# 05-GPS_IMU_SENSORS.net
KiCad netlist of a schematic drawn in Altium Designer
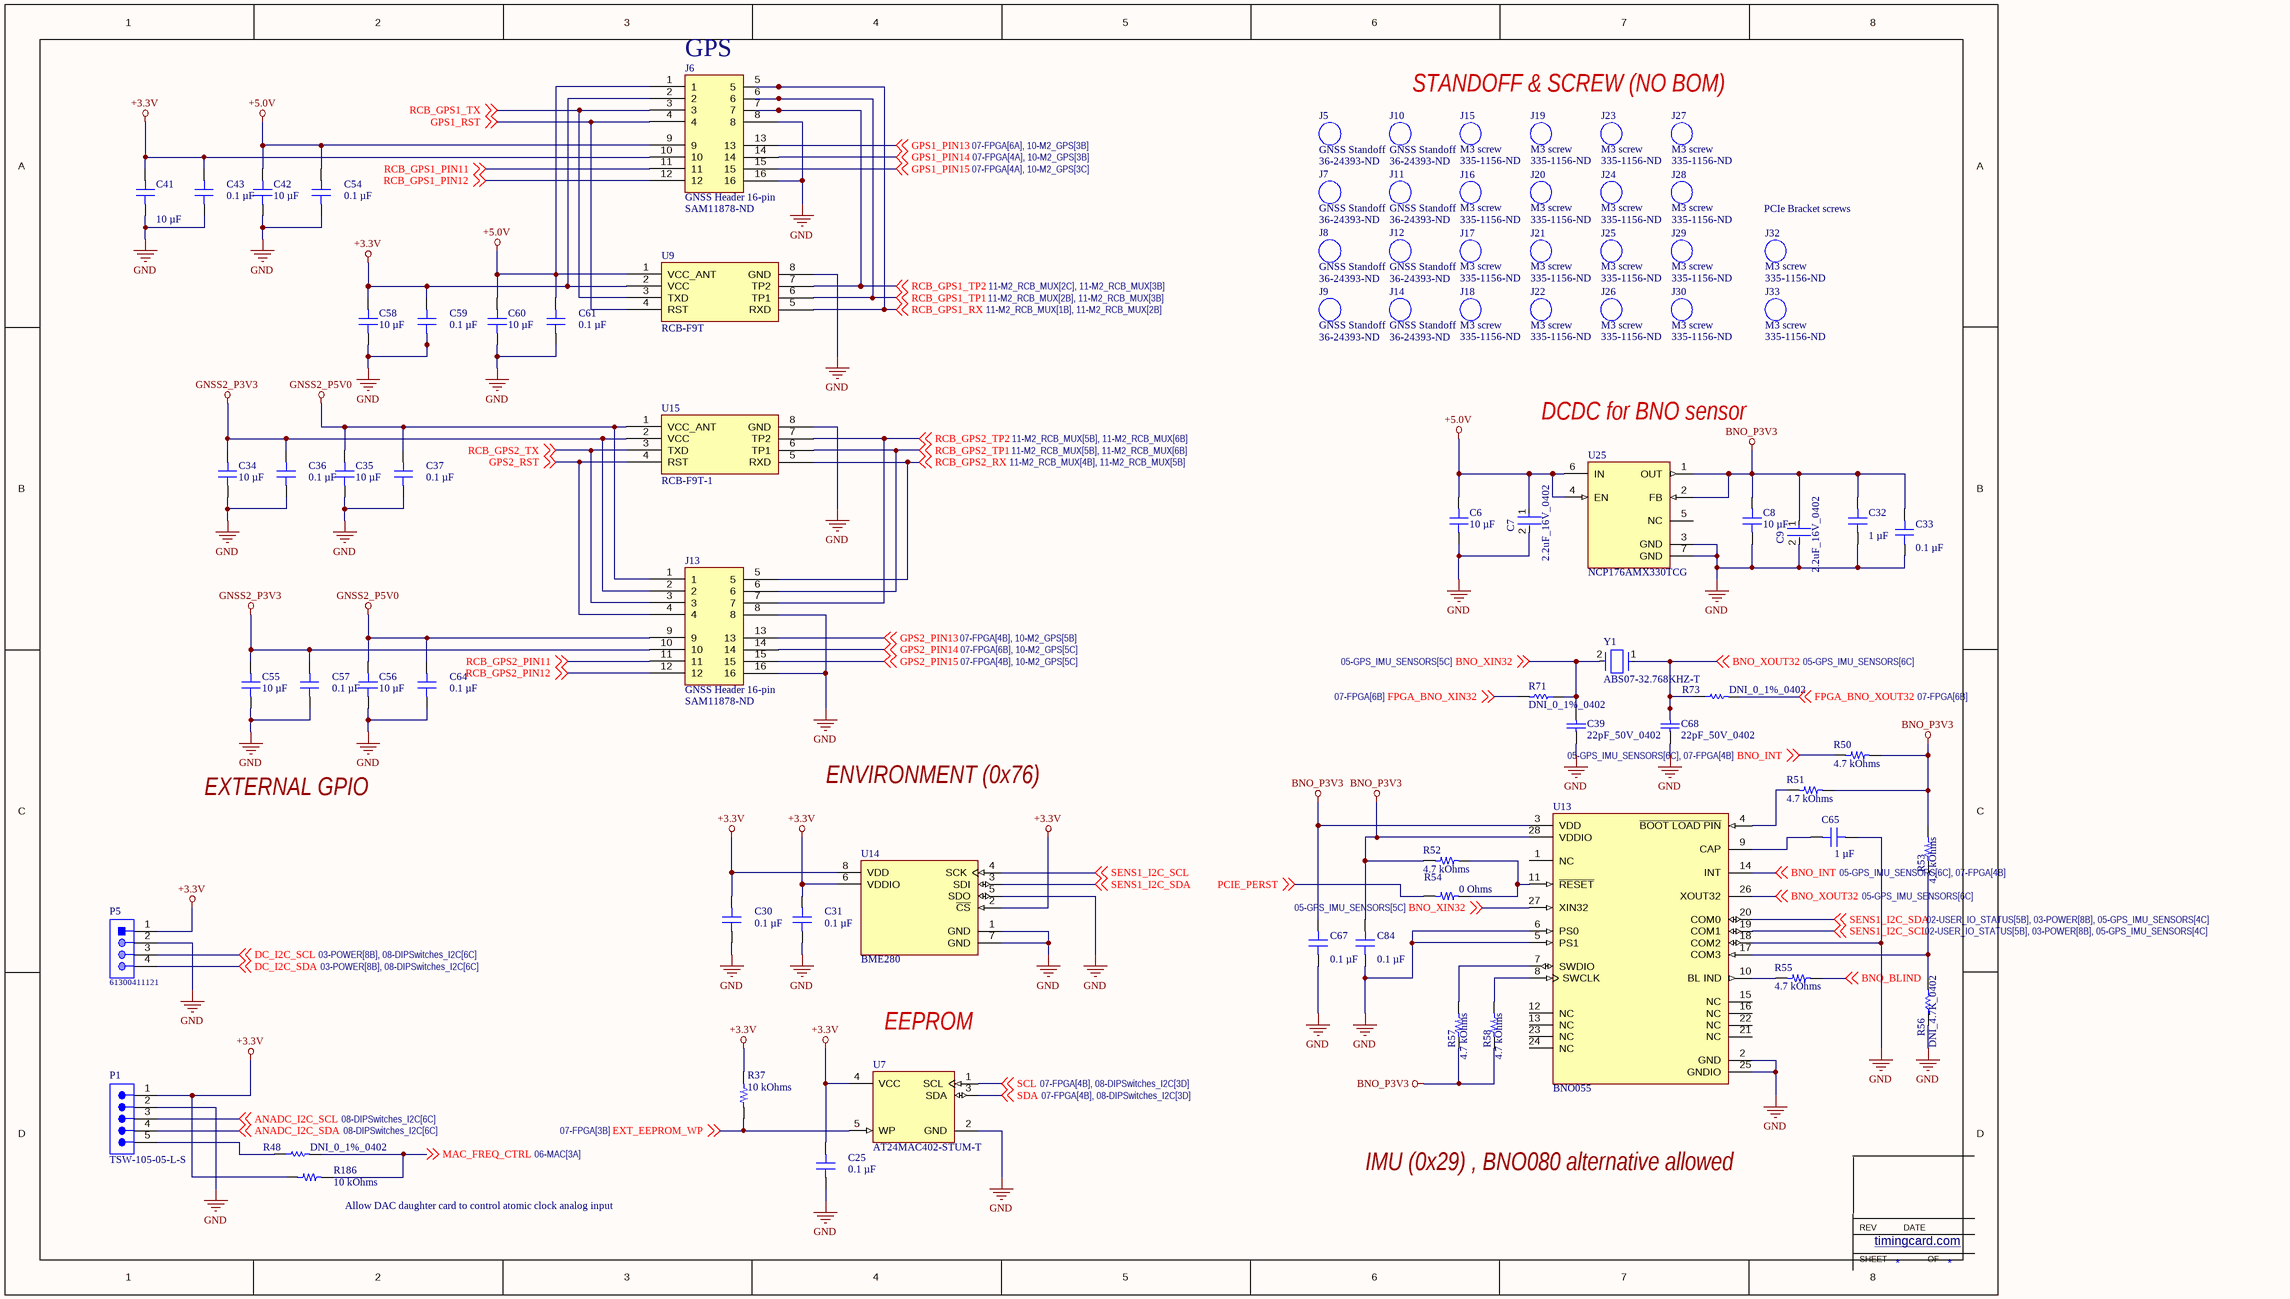
[diagram p0: 05-GPS_IMU_SENSORS.SchDoc]

(export (version "E")
  (design (tool "Eeschema 10.0.6"))
  (components
    (comp (ref "C6")
      (value "10 µF")
      (footprint "MURATA GRM21B 0805_2012")
      (description "CAP CER 10UF 25V X5R 0805")
      (fields (field (name "TOLERANCE") "±10%") (field (name "PART NUMBER") "GRM21BR61E106KA73L"))
      (libsource (lib "Celestial Altium Library - altium_library") (part "Capacitor"))
    )
    (comp (ref "C7")
      (value "2.2uF_16V_0402")
      (footprint "FP-C1005-050-0_05-IPC_A")
      (description "Multilayer Ceramic Capacitors 2.2μF ±10% 16V X5R SMD 0402")
      (fields (field (name "TOLERANCE") "10%"))
      (libsource (lib "Altium Content Vault") (part "b4654b650e69147ec39a6b967a45e02"))
    )
    (comp (ref "C8")
      (value "10 µF")
      (footprint "MURATA GRM21B 0805_2012")
      (description "CAP CER 10UF 25V X5R 0805")
      (fields (field (name "TOLERANCE") "±10%") (field (name "PART NUMBER") "GRM21BR61E106KA73L"))
      (libsource (lib "Celestial Altium Library - altium_library") (part "Capacitor"))
    )
    (comp (ref "C9")
      (value "2.2uF_16V_0402")
      (footprint "FP-C1005-050-0_05-IPC_A")
      (description "Multilayer Ceramic Capacitors 2.2μF ±10% 16V X5R SMD 0402")
      (fields (field (name "TOLERANCE") "10%"))
      (libsource (lib "Altium Content Vault") (part "b4654b650e69147ec39a6b967a45e02"))
    )
    (comp (ref "C25")
      (value "0.1 µF")
      (footprint "CAP 0402_1005")
      (description "CAP CER 0.1UF 50V X7R 0402")
      (fields (field (name "MANUFACTURER") "Yageo") (field (name "PART NUMBER") "CC0402KRX7R9BB104"))
      (libsource (lib "Celestial Altium Library - altium_library") (part "Capacitor"))
    )
    (comp (ref "C30")
      (value "0.1 µF")
      (footprint "CAP 0402_1005")
      (description "CAP CER 0.1UF 50V X7R 0402")
      (fields (field (name "MANUFACTURER") "Yageo") (field (name "PART NUMBER") "CC0402KRX7R9BB104"))
      (libsource (lib "Celestial Altium Library - altium_library") (part "Capacitor"))
    )
    (comp (ref "C31")
      (value "0.1 µF")
      (footprint "CAP 0402_1005")
      (description "CAP CER 0.1UF 50V X7R 0402")
      (fields (field (name "MANUFACTURER") "Yageo") (field (name "PART NUMBER") "CC0402KRX7R9BB104"))
      (libsource (lib "Celestial Altium Library - altium_library") (part "Capacitor"))
    )
    (comp (ref "C32")
      (value "1 µF")
      (footprint "CAP 0402_1005")
      (description "CAP CER 1UF 25V X5R 0402")
      (fields (field (name "TOLERANCE") "±10%") (field (name "PART NUMBER") "CC0402KRX5R8BB105"))
      (libsource (lib "Celestial Altium Library - altium_library") (part "Capacitor"))
    )
    (comp (ref "C33")
      (value "0.1 µF")
      (footprint "CAP 0402_1005")
      (description "CAP CER 0.1UF 50V X7R 0402")
      (fields (field (name "TOLERANCE") "±10%") (field (name "PART NUMBER") "CC0402KRX7R9BB104"))
      (libsource (lib "Celestial Altium Library - altium_library") (part "Capacitor"))
    )
    (comp (ref "C34")
      (value "10 µF")
      (footprint "MURATA GRM21B 0805_2012")
      (description "CAP CER 10UF 25V X5R 0805")
      (fields (field (name "TOLERANCE") "±10%") (field (name "PART NUMBER") "GRM21BR61E106KA73L"))
      (libsource (lib "Celestial Altium Library - altium_library") (part "Capacitor"))
    )
    (comp (ref "C35")
      (value "10 µF")
      (footprint "MURATA GRM21B 0805_2012")
      (description "CAP CER 10UF 25V X5R 0805")
      (fields (field (name "TOLERANCE") "±10%") (field (name "PART NUMBER") "GRM21BR61E106KA73L"))
      (libsource (lib "Celestial Altium Library - altium_library") (part "Capacitor"))
    )
    (comp (ref "C36")
      (value "0.1 µF")
      (footprint "CAP 0402_1005")
      (description "CAP CER 0.1UF 50V X7R 0402")
      (fields (field (name "MANUFACTURER") "Yageo") (field (name "PART NUMBER") "CC0402KRX7R9BB104"))
      (libsource (lib "Celestial Altium Library - altium_library") (part "Capacitor"))
    )
    (comp (ref "C37")
      (value "0.1 µF")
      (footprint "CAP 0402_1005")
      (description "CAP CER 0.1UF 50V X7R 0402")
      (fields (field (name "MANUFACTURER") "Yageo") (field (name "PART NUMBER") "CC0402KRX7R9BB104"))
      (libsource (lib "Celestial Altium Library - altium_library") (part "Capacitor"))
    )
    (comp (ref "C39")
      (value "22pF_50V_0402")
      (footprint "CAPC1005X55X25ML05T05")
      (description "Chip Capacitor, 22 pF, +/- 5%, 50 V, -55 to 125 degC, 0402 (1005 Metric), RoHS, Tape and Reel")
      (fields (field (name "MANUFACTURER") "Yageo") (field (name "TOLERANCE") "5%"))
      (libsource (lib "Altium Content Vault") (part "CAP-NP-2"))
    )
    (comp (ref "C41")
      (value "10 µF")
      (footprint "MURATA GRM21B 0805_2012")
      (description "CAP CER 10UF 25V X5R 0805")
      (fields (field (name "TOLERANCE") "±10%") (field (name "PART NUMBER") "GRM21BR61E106KA73L"))
      (libsource (lib "Celestial Altium Library - altium_library") (part "Capacitor"))
    )
    (comp (ref "C42")
      (value "10 µF")
      (footprint "MURATA GRM21B 0805_2012")
      (description "CAP CER 10UF 25V X5R 0805")
      (fields (field (name "TOLERANCE") "±10%") (field (name "PART NUMBER") "GRM21BR61E106KA73L"))
      (libsource (lib "Celestial Altium Library - altium_library") (part "Capacitor"))
    )
    (comp (ref "C43")
      (value "0.1 µF")
      (footprint "CAP 0402_1005")
      (description "CAP CER 0.1UF 50V X7R 0402")
      (fields (field (name "MANUFACTURER") "Yageo") (field (name "PART NUMBER") "CC0402KRX7R9BB104"))
      (libsource (lib "Celestial Altium Library - altium_library") (part "Capacitor"))
    )
    (comp (ref "C54")
      (value "0.1 µF")
      (footprint "CAP 0402_1005")
      (description "CAP CER 0.1UF 50V X7R 0402")
      (fields (field (name "MANUFACTURER") "Yageo") (field (name "PART NUMBER") "CC0402KRX7R9BB104"))
      (libsource (lib "Celestial Altium Library - altium_library") (part "Capacitor"))
    )
    (comp (ref "C55")
      (value "10 µF")
      (footprint "MURATA GRM21B 0805_2012")
      (description "CAP CER 10UF 25V X5R 0805")
      (fields (field (name "TOLERANCE") "±10%") (field (name "PART NUMBER") "GRM21BR61E106KA73L"))
      (libsource (lib "Celestial Altium Library - altium_library") (part "Capacitor"))
    )
    (comp (ref "C56")
      (value "10 µF")
      (footprint "MURATA GRM21B 0805_2012")
      (description "CAP CER 10UF 25V X5R 0805")
      (fields (field (name "TOLERANCE") "±10%") (field (name "PART NUMBER") "GRM21BR61E106KA73L"))
      (libsource (lib "Celestial Altium Library - altium_library") (part "Capacitor"))
    )
    (comp (ref "C57")
      (value "0.1 µF")
      (footprint "CAP 0402_1005")
      (description "CAP CER 0.1UF 50V X7R 0402")
      (fields (field (name "MANUFACTURER") "Yageo") (field (name "PART NUMBER") "CC0402KRX7R9BB104"))
      (libsource (lib "Celestial Altium Library - altium_library") (part "Capacitor"))
    )
    (comp (ref "C58")
      (value "10 µF")
      (footprint "MURATA GRM21B 0805_2012")
      (description "CAP CER 10UF 25V X5R 0805")
      (fields (field (name "TOLERANCE") "±10%") (field (name "PART NUMBER") "GRM21BR61E106KA73L"))
      (libsource (lib "Celestial Altium Library - altium_library") (part "Capacitor"))
    )
    (comp (ref "C59")
      (value "0.1 µF")
      (footprint "CAP 0402_1005")
      (description "CAP CER 0.1UF 50V X7R 0402")
      (fields (field (name "MANUFACTURER") "Yageo") (field (name "PART NUMBER") "CC0402KRX7R9BB104"))
      (libsource (lib "Celestial Altium Library - altium_library") (part "Capacitor"))
    )
    (comp (ref "C60")
      (value "10 µF")
      (footprint "MURATA GRM21B 0805_2012")
      (description "CAP CER 10UF 25V X5R 0805")
      (fields (field (name "TOLERANCE") "±10%") (field (name "PART NUMBER") "GRM21BR61E106KA73L"))
      (libsource (lib "Celestial Altium Library - altium_library") (part "Capacitor"))
    )
    (comp (ref "C61")
      (value "0.1 µF")
      (footprint "CAP 0402_1005")
      (description "CAP CER 0.1UF 50V X7R 0402")
      (fields (field (name "MANUFACTURER") "Yageo") (field (name "PART NUMBER") "CC0402KRX7R9BB104"))
      (libsource (lib "Celestial Altium Library - altium_library") (part "Capacitor"))
    )
    (comp (ref "C64")
      (value "0.1 µF")
      (footprint "CAP 0402_1005")
      (description "CAP CER 0.1UF 50V X7R 0402")
      (fields (field (name "MANUFACTURER") "Yageo") (field (name "PART NUMBER") "CC0402KRX7R9BB104"))
      (libsource (lib "Celestial Altium Library - altium_library") (part "Capacitor"))
    )
    (comp (ref "C65")
      (value "1 µF")
      (footprint "CAP 0402_1005")
      (description "CAP CER 1UF 25V X5R 0402")
      (fields (field (name "TOLERANCE") "±10%") (field (name "PART NUMBER") "CC0402KRX5R8BB105"))
      (libsource (lib "Celestial Altium Library - altium_library") (part "Capacitor"))
    )
    (comp (ref "C67")
      (value "0.1 µF")
      (footprint "CAP 0402_1005")
      (description "CAP CER 0.1UF 50V X7R 0402")
      (fields (field (name "PART NUMBER") "CC0402KRX7R9BB104") (field (name "MANUFACTURER") "Yageo"))
      (libsource (lib "Celestial Altium Library - altium_library") (part "Capacitor"))
    )
    (comp (ref "C68")
      (value "22pF_50V_0402")
      (footprint "CAPC1005X55X25ML05T05")
      (description "Chip Capacitor, 22 pF, +/- 5%, 50 V, -55 to 125 degC, 0402 (1005 Metric), RoHS, Tape and Reel")
      (fields (field (name "MANUFACTURER") "Yageo") (field (name "TOLERANCE") "5%"))
      (libsource (lib "Altium Content Vault") (part "CAP-NP-2"))
    )
    (comp (ref "C84")
      (value "0.1 µF")
      (footprint "CAP 0402_1005")
      (description "CAP CER 0.1UF 50V X7R 0402")
      (fields (field (name "PART NUMBER") "CC0402KRX7R9BB104") (field (name "MANUFACTURER") "Yageo"))
      (libsource (lib "Celestial Altium Library - altium_library") (part "Capacitor"))
    )
    (comp (ref "J5")
      (value "GNSS Standoff")
      (fields (field (name "SUPPLIER PART NUMBER 1") "36-24393-ND"))
      (libsource (lib "FPGA_CONN") (part "GNSS Standoff"))
    )
    (comp (ref "J6")
      (value "GNSS Header 16-pin")
      (footprint "GNSS Header 16-pin")
      (fields (field (name "SUPPLIER PART NUMBER 1") "SAM11878-ND"))
      (libsource (lib "FPGA_CONN") (part "GNSS Header 16-pin"))
    )
    (comp (ref "J7")
      (value "GNSS Standoff")
      (fields (field (name "SUPPLIER PART NUMBER 1") "36-24393-ND"))
      (libsource (lib "FPGA_CONN") (part "GNSS Standoff"))
    )
    (comp (ref "J8")
      (value "GNSS Standoff")
      (fields (field (name "SUPPLIER PART NUMBER 1") "36-24393-ND"))
      (libsource (lib "FPGA_CONN") (part "GNSS Standoff"))
    )
    (comp (ref "J9")
      (value "GNSS Standoff")
      (fields (field (name "SUPPLIER PART NUMBER 1") "36-24393-ND"))
      (libsource (lib "FPGA_CONN") (part "GNSS Standoff"))
    )
    (comp (ref "J10")
      (value "GNSS Standoff")
      (fields (field (name "SUPPLIER PART NUMBER 1") "36-24393-ND"))
      (libsource (lib "FPGA_CONN") (part "GNSS Standoff"))
    )
    (comp (ref "J11")
      (value "GNSS Standoff")
      (fields (field (name "SUPPLIER PART NUMBER 1") "36-24393-ND"))
      (libsource (lib "FPGA_CONN") (part "GNSS Standoff"))
    )
    (comp (ref "J12")
      (value "GNSS Standoff")
      (fields (field (name "SUPPLIER PART NUMBER 1") "36-24393-ND"))
      (libsource (lib "FPGA_CONN") (part "GNSS Standoff"))
    )
    (comp (ref "J13")
      (value "GNSS Header 16-pin")
      (footprint "GNSS Header 16-pin")
      (fields (field (name "SUPPLIER PART NUMBER 1") "SAM11878-ND"))
      (libsource (lib "FPGA_CONN") (part "GNSS Header 16-pin"))
    )
    (comp (ref "J14")
      (value "GNSS Standoff")
      (fields (field (name "SUPPLIER PART NUMBER 1") "36-24393-ND"))
      (libsource (lib "FPGA_CONN") (part "GNSS Standoff"))
    )
    (comp (ref "J15")
      (value "M3 screw")
      (fields (field (name "SUPPLIER PART NUMBER 1") "335-1156-ND"))
      (libsource (lib "FPGA_CONN") (part "M3 screw"))
    )
    (comp (ref "J16")
      (value "M3 screw")
      (fields (field (name "SUPPLIER PART NUMBER 1") "335-1156-ND"))
      (libsource (lib "FPGA_CONN") (part "M3 screw"))
    )
    (comp (ref "J17")
      (value "M3 screw")
      (fields (field (name "SUPPLIER PART NUMBER 1") "335-1156-ND"))
      (libsource (lib "FPGA_CONN") (part "M3 screw"))
    )
    (comp (ref "J18")
      (value "M3 screw")
      (fields (field (name "SUPPLIER PART NUMBER 1") "335-1156-ND"))
      (libsource (lib "FPGA_CONN") (part "M3 screw"))
    )
    (comp (ref "J19")
      (value "M3 screw")
      (fields (field (name "SUPPLIER PART NUMBER 1") "335-1156-ND"))
      (libsource (lib "FPGA_CONN") (part "M3 screw"))
    )
    (comp (ref "J20")
      (value "M3 screw")
      (fields (field (name "SUPPLIER PART NUMBER 1") "335-1156-ND"))
      (libsource (lib "FPGA_CONN") (part "M3 screw"))
    )
    (comp (ref "J21")
      (value "M3 screw")
      (fields (field (name "SUPPLIER PART NUMBER 1") "335-1156-ND"))
      (libsource (lib "FPGA_CONN") (part "M3 screw"))
    )
    (comp (ref "J22")
      (value "M3 screw")
      (fields (field (name "SUPPLIER PART NUMBER 1") "335-1156-ND"))
      (libsource (lib "FPGA_CONN") (part "M3 screw"))
    )
    (comp (ref "J23")
      (value "M3 screw")
      (fields (field (name "SUPPLIER PART NUMBER 1") "335-1156-ND"))
      (libsource (lib "FPGA_CONN") (part "M3 screw"))
    )
    (comp (ref "J24")
      (value "M3 screw")
      (fields (field (name "SUPPLIER PART NUMBER 1") "335-1156-ND"))
      (libsource (lib "FPGA_CONN") (part "M3 screw"))
    )
    (comp (ref "J25")
      (value "M3 screw")
      (fields (field (name "SUPPLIER PART NUMBER 1") "335-1156-ND"))
      (libsource (lib "FPGA_CONN") (part "M3 screw"))
    )
    (comp (ref "J26")
      (value "M3 screw")
      (fields (field (name "SUPPLIER PART NUMBER 1") "335-1156-ND"))
      (libsource (lib "FPGA_CONN") (part "M3 screw"))
    )
    (comp (ref "J27")
      (value "M3 screw")
      (fields (field (name "SUPPLIER PART NUMBER 1") "335-1156-ND"))
      (libsource (lib "FPGA_CONN") (part "M3 screw"))
    )
    (comp (ref "J28")
      (value "M3 screw")
      (fields (field (name "SUPPLIER PART NUMBER 1") "335-1156-ND"))
      (libsource (lib "FPGA_CONN") (part "M3 screw"))
    )
    (comp (ref "J29")
      (value "M3 screw")
      (fields (field (name "SUPPLIER PART NUMBER 1") "335-1156-ND"))
      (libsource (lib "FPGA_CONN") (part "M3 screw"))
    )
    (comp (ref "J30")
      (value "M3 screw")
      (fields (field (name "SUPPLIER PART NUMBER 1") "335-1156-ND"))
      (libsource (lib "FPGA_CONN") (part "M3 screw"))
    )
    (comp (ref "J32")
      (value "M3 screw")
      (fields (field (name "SUPPLIER PART NUMBER 1") "335-1156-ND"))
      (libsource (lib "FPGA_CONN") (part "M3 screw"))
    )
    (comp (ref "J33")
      (value "M3 screw")
      (fields (field (name "SUPPLIER PART NUMBER 1") "335-1156-ND"))
      (libsource (lib "FPGA_CONN") (part "M3 screw"))
    )
    (comp (ref "P1")
      (value "TSW-105-05-L-S")
      (footprint "SMTC-TSW-105-05-X-S")
      (description "0.025\" SQ Post Header, Through-hole, Vertical, -55 to 125 degC, 2.54 mm Pitch, 5-Pin, Male, RoHS")
      (fields (field (name "MANUFACTURER") "Samtec"))
      (libsource (lib "Altium Content Vault") (part "SMTC-TSW-105-05-X-S"))
    )
    (comp (ref "P5")
      (value "61300411121")
      (footprint "61300411121")
      (description "THT Vertical Pin Header WR-PHD, Pitch 2.54 mm, Single Row, 4 pins")
      (fields (field (name "MANUFACTURER") "Wurth Elektronik") (field (name "PUBLISHER") "WurthElektronik"))
      (libsource (lib "Altium Content Vault") (part "WE-CN-1P-M-R4"))
    )
    (comp (ref "R37")
      (value "10 kOhms")
      (footprint "YAGEO RES 0402_1005")
      (description "RES 10K OHM 1% 1/16W 0402")
      (fields (field (name "TOLERANCE") "±1%") (field (name "MANUFACTURER") "Yageo"))
      (libsource (lib "Celestial Altium Library - altium_library") (part "Resistor"))
    )
    (comp (ref "R48")
      (value "DNI_0_1%_0402")
      (footprint "RESC1005X40X25LL05T05")
      (description "Chip Resistor, 0 Ohm, 0.1 W, -55 to 155 degC, 0402 (1005 Metric), RoHS, Tape and Reel")
      (fields (field (name "MANUFACTURER") "Panasonic") (field (name "TOLERANCE") "5%"))
      (libsource (lib "Altium Content Vault") (part "RES-2"))
    )
    (comp (ref "R50")
      (value "4.7 kOhms")
      (footprint "YAGEO RES 0402_1005")
      (description "RES 4.7K OHM 1% 1/16W 0402")
      (fields (field (name "TOLERANCE") "±1%") (field (name "PART NUMBER") "RC0402FR-074K7L"))
      (libsource (lib "Celestial Altium Library - altium_library") (part "Resistor"))
    )
    (comp (ref "R51")
      (value "4.7 kOhms")
      (footprint "YAGEO RES 0402_1005")
      (description "RES 4.7K OHM 1% 1/16W 0402")
      (fields (field (name "TOLERANCE") "±1%") (field (name "PART NUMBER") "RC0402FR-074K7L"))
      (libsource (lib "Celestial Altium Library - altium_library") (part "Resistor"))
    )
    (comp (ref "R52")
      (value "4.7 kOhms")
      (footprint "YAGEO RES 0402_1005")
      (description "RES 4.7K OHM 1% 1/16W 0402")
      (fields (field (name "TOLERANCE") "±1%") (field (name "PART NUMBER") "RC0402FR-074K7L"))
      (libsource (lib "Celestial Altium Library - altium_library") (part "Resistor"))
    )
    (comp (ref "R53")
      (value "4.7 kOhms")
      (footprint "YAGEO RES 0402_1005")
      (description "RES 4.7K OHM 1% 1/16W 0402")
      (fields (field (name "TOLERANCE") "±1%") (field (name "PART NUMBER") "RC0402FR-074K7L"))
      (libsource (lib "Celestial Altium Library - altium_library") (part "Resistor"))
    )
    (comp (ref "R54")
      (value "0 Ohms")
      (footprint "YAGEO RES 0402_1005")
      (description "RES 0 OHM JUMPER 1/16W 0402")
      (fields (field (name "MANUFACTURER") "Yageo") (field (name "TOLERANCE") "Jumper"))
      (libsource (lib "Celestial Altium Library - altium_library") (part "Resistor"))
    )
    (comp (ref "R55")
      (value "4.7 kOhms")
      (footprint "YAGEO RES 0402_1005")
      (description "RES 4.7K OHM 1% 1/16W 0402")
      (fields (field (name "TOLERANCE") "±1%") (field (name "PART NUMBER") "RC0402FR-074K7L"))
      (libsource (lib "Celestial Altium Library - altium_library") (part "Resistor"))
    )
    (comp (ref "R56")
      (value "DNI_4.7K_0402")
      (footprint "RESC1005X40X25LL05T05")
      (description "Chip Resistor, 4.7 KOhm, +/- 1%, 0.1 W, -55 to 155 degC, 0402 (1005 Metric), RoHS, Tape and Reel")
      (fields (field (name "TOLERANCE") "1%") (field (name "PARTNUMBER") "ERJ-2RKF4701X"))
      (libsource (lib "Altium Content Vault") (part "RES-2"))
    )
    (comp (ref "R57")
      (value "4.7 kOhms")
      (footprint "YAGEO RES 0402_1005")
      (description "RES 4.7K OHM 1% 1/16W 0402")
      (fields (field (name "TOLERANCE") "±1%") (field (name "PART NUMBER") "RC0402FR-074K7L"))
      (libsource (lib "Celestial Altium Library - altium_library") (part "Resistor"))
    )
    (comp (ref "R58")
      (value "4.7 kOhms")
      (footprint "YAGEO RES 0402_1005")
      (description "RES 4.7K OHM 1% 1/16W 0402")
      (fields (field (name "TOLERANCE") "±1%") (field (name "PART NUMBER") "RC0402FR-074K7L"))
      (libsource (lib "Celestial Altium Library - altium_library") (part "Resistor"))
    )
    (comp (ref "R71")
      (value "DNI_0_1%_0402")
      (footprint "RESC1005X40X25LL05T05")
      (description "Chip Resistor, 0 Ohm, 0.1 W, -55 to 155 degC, 0402 (1005 Metric), RoHS, Tape and Reel")
      (fields (field (name "MANUFACTURER") "Panasonic") (field (name "TOLERANCE") "5%"))
      (libsource (lib "Altium Content Vault") (part "RES-2"))
    )
    (comp (ref "R73")
      (value "DNI_0_1%_0402")
      (footprint "RESC1005X40X25LL05T05")
      (description "Chip Resistor, 0 Ohm, 0.1 W, -55 to 155 degC, 0402 (1005 Metric), RoHS, Tape and Reel")
      (fields (field (name "MANUFACTURER") "Panasonic") (field (name "TOLERANCE") "5%"))
      (libsource (lib "Altium Content Vault") (part "RES-2"))
    )
    (comp (ref "R186")
      (value "10 kOhms")
      (footprint "YAGEO RES 0402_1005")
      (description "RES 10K OHM 1% 1/16W 0402")
      (fields (field (name "PART NUMBER") "RC0402FR-0710KL") (field (name "MANUFACTURER") "Yageo"))
      (libsource (lib "Celestial Altium Library - altium_library") (part "Resistor"))
    )
    (comp (ref "U7")
      (value "AT24MAC402-STUM-T")
      (footprint "FP-5TS1-IPC_C")
      (description "IC EEPROM 2K I2C 1MHZ SOT23-5")
      (fields
        (field (name "MANUFACTURER") "Microchip")
        (field (name "OCTOPART") "https://octopart.com/at24mac402-stum-t-microchip-77758112")
      )
      (libsource (lib "Altium Content Vault") (part "93fe34f5f049140596bab6421a6454b"))
    )
    (comp (ref "U9")
      (value "RCB-F9T")
      (footprint "GNSS")
      (description "MOD, GPS")
      (fields (field (name "VELENTIUM PART NUM") "<V PART NUM>"))
      (libsource (lib "Modules") (part "RCB-F9T"))
    )
    (comp (ref "U13")
      (value "BNO055")
      (footprint "FP-BNO055-MFG")
      (description "IMU ACCEL/GYRO/MAG I2C 28LGA")
      (libsource (lib "Altium Content Vault") (part "ba837af00a0b6167256f888b31462b1"))
    )
    (comp (ref "U14")
      (value "BME280")
      (footprint "FP-BME280-MFG")
      (description "SENSOR PRESSURE HUMIDITY TEMP")
      (libsource (lib "Altium Content Vault") (part "d58e2f6669bc67e6a2bc6a28610ca79"))
    )
    (comp (ref "U15")
      (value "RCB-F9T-1")
      (footprint "GNSS")
      (description "MOD, GPS")
      (fields (field (name "VELENTIUM PART NUM") "<V PART NUM>"))
      (libsource (lib "Modules") (part "RCB-F9T"))
    )
    (comp (ref "U25")
      (value "NCP176AMX330TCG")
      (footprint "FP-711AT-MFG")
      (description "IC REG LINEAR 3.3V 500MA 6XDFN")
      (fields
        (field (name "MANUFACTURER") "ON Semiconductor")
        (field (name "OCTOPART") "https://octopart.com/ncp176amx330tcg-on+semiconductor-61522616")
      )
      (libsource (lib "Altium Content Vault") (part "a38d0f79c2a9f01c07a7e52882ed186"))
    )
    (comp (ref "Y1")
      (value "ABS07-32.768KHZ-T")
      (footprint "FP-ABS07-MFG")
      (description "Crystal 32.768kHz ±20ppm (Tol) 12.5pF FUND 70kΩ 2-Pin CSMD T/R")
      (fields (field (name "TOLERANCE") "20ppm"))
      (libsource (lib "Altium Content Vault") (part "c23a69dc6c9e2f18f2079038eb95dd1"))
    )
  )
  (nets
    (net (code "1") (name "+3.3V") (class "Default")
      (node (ref "C25") (pin "2") (pinfunction "2_2") (pintype "passive"))
      (node (ref "C30") (pin "2") (pinfunction "2_2") (pintype "passive"))
      (node (ref "C31") (pin "2") (pinfunction "2_2") (pintype "passive"))
      (node (ref "C41") (pin "2") (pinfunction "2_2") (pintype "passive"))
      (node (ref "C43") (pin "2") (pinfunction "2_2") (pintype "passive"))
      (node (ref "C58") (pin "2") (pinfunction "2_2") (pintype "passive"))
      (node (ref "C59") (pin "2") (pinfunction "2_2") (pintype "passive"))
      (node (ref "J6") (pin "10") (pinfunction "10_10") (pintype "passive"))
      (node (ref "J6") (pin "2") (pinfunction "2_2") (pintype "passive"))
      (node (ref "P1") (pin "1") (pinfunction "1_1") (pintype "passive"))
      (node (ref "P5") (pin "1") (pinfunction "1_1") (pintype "passive"))
      (node (ref "R186") (pin "1") (pinfunction "1_1") (pintype "passive"))
      (node (ref "R37") (pin "2") (pinfunction "2_2") (pintype "passive"))
      (node (ref "U14") (pin "2") (pinfunction "~{CS}_2") (pintype "input"))
      (node (ref "U14") (pin "6") (pinfunction "VDDIO_6") (pintype "power_in"))
      (node (ref "U14") (pin "8") (pinfunction "VDD_8") (pintype "power_in"))
      (node (ref "U7") (pin "4") (pinfunction "VCC_4") (pintype "power_in"))
      (node (ref "U9") (pin "2") (pinfunction "VCC_2") (pintype "passive"))
    )
    (net (code "2") (name "+5.0V") (class "Default")
      (node (ref "C42") (pin "2") (pinfunction "2_2") (pintype "passive"))
      (node (ref "C54") (pin "2") (pinfunction "2_2") (pintype "passive"))
      (node (ref "C6") (pin "2") (pinfunction "2_2") (pintype "passive"))
      (node (ref "C60") (pin "2") (pinfunction "2_2") (pintype "passive"))
      (node (ref "C61") (pin "2") (pinfunction "2_2") (pintype "passive"))
      (node (ref "C7") (pin "1") (pinfunction "1_1") (pintype "passive"))
      (node (ref "J6") (pin "1") (pinfunction "1_1") (pintype "passive"))
      (node (ref "J6") (pin "9") (pinfunction "9_9") (pintype "passive"))
      (node (ref "U25") (pin "4") (pinfunction "EN_4") (pintype "input"))
      (node (ref "U25") (pin "6") (pinfunction "IN_6") (pintype "power_in"))
      (node (ref "U9") (pin "1") (pinfunction "VCC_ANT_1") (pintype "passive"))
    )
    (net (code "3") (name "ANADC_I2C_SCL") (class "Default")
      (node (ref "P1") (pin "3") (pinfunction "3_3") (pintype "passive"))
    )
    (net (code "4") (name "ANADC_I2C_SDA") (class "Default")
      (node (ref "P1") (pin "4") (pinfunction "4_4") (pintype "passive"))
    )
    (net (code "5") (name "BNO_BLIND") (class "Default")
      (node (ref "R55") (pin "1") (pinfunction "1_1") (pintype "passive"))
    )
    (net (code "6") (name "BNO_INT") (class "Default")
      (node (ref "R50") (pin "2") (pinfunction "2_2") (pintype "passive"))
      (node (ref "U13") (pin "14") (pinfunction "INT_14") (pintype "passive"))
    )
    (net (code "7") (name "BNO_P3V3") (class "Default")
      (node (ref "C32") (pin "2") (pinfunction "2_2") (pintype "passive"))
      (node (ref "C33") (pin "1") (pinfunction "1_1") (pintype "passive"))
      (node (ref "C67") (pin "2") (pinfunction "2_2") (pintype "passive"))
      (node (ref "C8") (pin "2") (pinfunction "2_2") (pintype "passive"))
      (node (ref "C84") (pin "2") (pinfunction "2_2") (pintype "passive"))
      (node (ref "C9") (pin "1") (pinfunction "1_1") (pintype "passive"))
      (node (ref "R50") (pin "1") (pinfunction "1_1") (pintype "passive"))
      (node (ref "R51") (pin "1") (pinfunction "1_1") (pintype "passive"))
      (node (ref "R52") (pin "2") (pinfunction "2_2") (pintype "passive"))
      (node (ref "R53") (pin "2") (pinfunction "2_2") (pintype "passive"))
      (node (ref "R57") (pin "1") (pinfunction "1_1") (pintype "passive"))
      (node (ref "R58") (pin "1") (pinfunction "1_1") (pintype "passive"))
      (node (ref "U13") (pin "28") (pinfunction "VDDIO_28") (pintype "power_in"))
      (node (ref "U13") (pin "3") (pinfunction "VDD_3") (pintype "power_in"))
      (node (ref "U25") (pin "1") (pinfunction "OUT_1") (pintype "output"))
      (node (ref "U25") (pin "2") (pinfunction "FB_2") (pintype "input"))
    )
    (net (code "8") (name "BNO_XIN32") (class "Default")
      (node (ref "C39") (pin "2") (pinfunction "2_2") (pintype "passive"))
      (node (ref "R71") (pin "1") (pinfunction "1_1") (pintype "passive"))
      (node (ref "U13") (pin "27") (pinfunction "XIN32_27") (pintype "input"))
      (node (ref "Y1") (pin "2") (pinfunction "2_2") (pintype "passive"))
    )
    (net (code "9") (name "BNO_XOUT32") (class "Default")
      (node (ref "C68") (pin "2") (pinfunction "2_2") (pintype "passive"))
      (node (ref "R73") (pin "1") (pinfunction "1_1") (pintype "passive"))
      (node (ref "U13") (pin "26") (pinfunction "XOUT32_26") (pintype "passive"))
      (node (ref "Y1") (pin "1") (pinfunction "1_1") (pintype "passive"))
    )
    (net (code "10") (name "DC_I2C_SCL") (class "Default")
      (node (ref "P5") (pin "3") (pinfunction "3_3") (pintype "passive"))
    )
    (net (code "11") (name "DC_I2C_SDA") (class "Default")
      (node (ref "P5") (pin "4") (pinfunction "4_4") (pintype "passive"))
    )
    (net (code "12") (name "EXT_EEPROM_WP") (class "Default")
      (node (ref "R37") (pin "1") (pinfunction "1_1") (pintype "passive"))
      (node (ref "U7") (pin "5") (pinfunction "WP_5") (pintype "input"))
    )
    (net (code "13") (name "FPGA_BNO_XIN32") (class "Default")
      (node (ref "R71") (pin "2") (pinfunction "2_2") (pintype "passive"))
    )
    (net (code "14") (name "FPGA_BNO_XOUT32") (class "Default")
      (node (ref "R73") (pin "2") (pinfunction "2_2") (pintype "passive"))
    )
    (net (code "15") (name "GND") (class "Default")
      (node (ref "C25") (pin "1") (pinfunction "1_1") (pintype "passive"))
      (node (ref "C30") (pin "1") (pinfunction "1_1") (pintype "passive"))
      (node (ref "C31") (pin "1") (pinfunction "1_1") (pintype "passive"))
      (node (ref "C32") (pin "1") (pinfunction "1_1") (pintype "passive"))
      (node (ref "C33") (pin "2") (pinfunction "2_2") (pintype "passive"))
      (node (ref "C34") (pin "1") (pinfunction "1_1") (pintype "passive"))
      (node (ref "C35") (pin "1") (pinfunction "1_1") (pintype "passive"))
      (node (ref "C36") (pin "1") (pinfunction "1_1") (pintype "passive"))
      (node (ref "C37") (pin "1") (pinfunction "1_1") (pintype "passive"))
      (node (ref "C39") (pin "1") (pinfunction "1_1") (pintype "passive"))
      (node (ref "C41") (pin "1") (pinfunction "1_1") (pintype "passive"))
      (node (ref "C42") (pin "1") (pinfunction "1_1") (pintype "passive"))
      (node (ref "C43") (pin "1") (pinfunction "1_1") (pintype "passive"))
      (node (ref "C54") (pin "1") (pinfunction "1_1") (pintype "passive"))
      (node (ref "C55") (pin "1") (pinfunction "1_1") (pintype "passive"))
      (node (ref "C56") (pin "1") (pinfunction "1_1") (pintype "passive"))
      (node (ref "C57") (pin "1") (pinfunction "1_1") (pintype "passive"))
      (node (ref "C58") (pin "1") (pinfunction "1_1") (pintype "passive"))
      (node (ref "C59") (pin "1") (pinfunction "1_1") (pintype "passive"))
      (node (ref "C6") (pin "1") (pinfunction "1_1") (pintype "passive"))
      (node (ref "C60") (pin "1") (pinfunction "1_1") (pintype "passive"))
      (node (ref "C61") (pin "1") (pinfunction "1_1") (pintype "passive"))
      (node (ref "C64") (pin "1") (pinfunction "1_1") (pintype "passive"))
      (node (ref "C65") (pin "1") (pinfunction "1_1") (pintype "passive"))
      (node (ref "C67") (pin "1") (pinfunction "1_1") (pintype "passive"))
      (node (ref "C68") (pin "1") (pinfunction "1_1") (pintype "passive"))
      (node (ref "C7") (pin "2") (pinfunction "2_2") (pintype "passive"))
      (node (ref "C8") (pin "1") (pinfunction "1_1") (pintype "passive"))
      (node (ref "C84") (pin "1") (pinfunction "1_1") (pintype "passive"))
      (node (ref "C9") (pin "2") (pinfunction "2_2") (pintype "passive"))
      (node (ref "J13") (pin "16") (pinfunction "16_16") (pintype "passive"))
      (node (ref "J13") (pin "8") (pinfunction "8_8") (pintype "passive"))
      (node (ref "J6") (pin "16") (pinfunction "16_16") (pintype "passive"))
      (node (ref "J6") (pin "8") (pinfunction "8_8") (pintype "passive"))
      (node (ref "P1") (pin "2") (pinfunction "2_2") (pintype "passive"))
      (node (ref "P5") (pin "2") (pinfunction "2_2") (pintype "passive"))
      (node (ref "R56") (pin "1") (pinfunction "1_1") (pintype "passive"))
      (node (ref "U13") (pin "18") (pinfunction "COM2_18") (pintype "bidirectional"))
      (node (ref "U13") (pin "2") (pinfunction "GND_2") (pintype "power_in"))
      (node (ref "U13") (pin "25") (pinfunction "GNDIO_25") (pintype "power_in"))
      (node (ref "U13") (pin "5") (pinfunction "PS1_5") (pintype "input"))
      (node (ref "U13") (pin "6") (pinfunction "PS0_6") (pintype "input"))
      (node (ref "U14") (pin "1") (pinfunction "GND_1") (pintype "power_in"))
      (node (ref "U14") (pin "5") (pinfunction "SDO_5") (pintype "bidirectional"))
      (node (ref "U14") (pin "7") (pinfunction "GND_7") (pintype "power_in"))
      (node (ref "U15") (pin "8") (pinfunction "GND_8") (pintype "passive"))
      (node (ref "U25") (pin "3") (pinfunction "GND_3") (pintype "power_in"))
      (node (ref "U25") (pin "7") (pinfunction "GND_7") (pintype "power_in"))
      (node (ref "U7") (pin "2") (pinfunction "GND_2") (pintype "power_in"))
      (node (ref "U9") (pin "8") (pinfunction "GND_8") (pintype "passive"))
    )
    (net (code "16") (name "GNSS2_P3V3") (class "Default")
      (node (ref "C34") (pin "2") (pinfunction "2_2") (pintype "passive"))
      (node (ref "C36") (pin "2") (pinfunction "2_2") (pintype "passive"))
      (node (ref "C55") (pin "2") (pinfunction "2_2") (pintype "passive"))
      (node (ref "C57") (pin "2") (pinfunction "2_2") (pintype "passive"))
      (node (ref "J13") (pin "10") (pinfunction "10_10") (pintype "passive"))
      (node (ref "J13") (pin "2") (pinfunction "2_2") (pintype "passive"))
      (node (ref "U15") (pin "2") (pinfunction "VCC_2") (pintype "passive"))
    )
    (net (code "17") (name "GNSS2_P5V0") (class "Default")
      (node (ref "C35") (pin "2") (pinfunction "2_2") (pintype "passive"))
      (node (ref "C37") (pin "2") (pinfunction "2_2") (pintype "passive"))
      (node (ref "C56") (pin "2") (pinfunction "2_2") (pintype "passive"))
      (node (ref "C64") (pin "2") (pinfunction "2_2") (pintype "passive"))
      (node (ref "J13") (pin "1") (pinfunction "1_1") (pintype "passive"))
      (node (ref "J13") (pin "9") (pinfunction "9_9") (pintype "passive"))
      (node (ref "U15") (pin "1") (pinfunction "VCC_ANT_1") (pintype "passive"))
    )
    (net (code "18") (name "GPS1_PIN13") (class "Default")
      (node (ref "J6") (pin "13") (pinfunction "13_13") (pintype "passive"))
    )
    (net (code "19") (name "GPS1_PIN14") (class "Default")
      (node (ref "J6") (pin "14") (pinfunction "14_14") (pintype "passive"))
    )
    (net (code "20") (name "GPS1_PIN15") (class "Default")
      (node (ref "J6") (pin "15") (pinfunction "15_15") (pintype "passive"))
    )
    (net (code "21") (name "GPS1_RST") (class "Default")
      (node (ref "J6") (pin "4") (pinfunction "4_4") (pintype "passive"))
      (node (ref "U9") (pin "4") (pinfunction "RST_4") (pintype "passive"))
    )
    (net (code "22") (name "GPS2_PIN13") (class "Default")
      (node (ref "J13") (pin "13") (pinfunction "13_13") (pintype "passive"))
    )
    (net (code "23") (name "GPS2_PIN14") (class "Default")
      (node (ref "J13") (pin "14") (pinfunction "14_14") (pintype "passive"))
    )
    (net (code "24") (name "GPS2_PIN15") (class "Default")
      (node (ref "J13") (pin "15") (pinfunction "15_15") (pintype "passive"))
    )
    (net (code "25") (name "GPS2_RST") (class "Default")
      (node (ref "J13") (pin "4") (pinfunction "4_4") (pintype "passive"))
      (node (ref "U15") (pin "4") (pinfunction "RST_4") (pintype "passive"))
    )
    (net (code "26") (name "MAC_FREQ_CTRL") (class "Default")
      (node (ref "R186") (pin "2") (pinfunction "2_2") (pintype "passive"))
      (node (ref "R48") (pin "2") (pinfunction "2_2") (pintype "passive"))
    )
    (net (code "27") (name "Net-(P1-Pad5)") (class "Default")
      (node (ref "P1") (pin "5") (pinfunction "5_5") (pintype "passive"))
      (node (ref "R48") (pin "1") (pinfunction "1_1") (pintype "passive"))
    )
    (net (code "28") (name "Net-(U13-BL_IND)") (class "Default")
      (node (ref "R55") (pin "2") (pinfunction "2_2") (pintype "passive"))
      (node (ref "U13") (pin "10") (pinfunction "BL_IND_10") (pintype "output"))
    )
    (net (code "29") (name "Net-(U13-CAP)") (class "Default")
      (node (ref "C65") (pin "2") (pinfunction "2_2") (pintype "passive"))
      (node (ref "U13") (pin "9") (pinfunction "CAP_9") (pintype "passive"))
    )
    (net (code "30") (name "Net-(U13-COM3)") (class "Default")
      (node (ref "R53") (pin "1") (pinfunction "1_1") (pintype "passive"))
      (node (ref "R56") (pin "2") (pinfunction "2_2") (pintype "passive"))
      (node (ref "U13") (pin "17") (pinfunction "COM3_17") (pintype "input"))
    )
    (net (code "31") (name "Net-(U13-SWCLK)") (class "Default")
      (node (ref "R58") (pin "2") (pinfunction "2_2") (pintype "passive"))
      (node (ref "U13") (pin "8") (pinfunction "SWCLK_8") (pintype "input"))
    )
    (net (code "32") (name "Net-(U13-SWDIO)") (class "Default")
      (node (ref "R57") (pin "2") (pinfunction "2_2") (pintype "passive"))
      (node (ref "U13") (pin "7") (pinfunction "SWDIO_7") (pintype "bidirectional"))
    )
    (net (code "33") (name "Net-(U13-~{BOOT_LOAD_PIN})") (class "Default")
      (node (ref "R51") (pin "2") (pinfunction "2_2") (pintype "passive"))
      (node (ref "U13") (pin "4") (pinfunction "~{BOOT_LOAD_PIN}_4") (pintype "input"))
    )
    (net (code "34") (name "Net-(U13-~{RESET})") (class "Default")
      (node (ref "R52") (pin "1") (pinfunction "1_1") (pintype "passive"))
      (node (ref "R54") (pin "2") (pinfunction "2_2") (pintype "passive"))
      (node (ref "U13") (pin "11") (pinfunction "~{RESET}_11") (pintype "input"))
    )
    (net (code "35") (name "PCIE_PERST") (class "Default")
      (node (ref "R54") (pin "1") (pinfunction "1_1") (pintype "passive"))
    )
    (net (code "36") (name "RCB_GPS1_PIN11") (class "Default")
      (node (ref "J6") (pin "11") (pinfunction "11_11") (pintype "passive"))
    )
    (net (code "37") (name "RCB_GPS1_PIN12") (class "Default")
      (node (ref "J6") (pin "12") (pinfunction "12_12") (pintype "passive"))
    )
    (net (code "38") (name "RCB_GPS1_RX") (class "Default")
      (node (ref "J6") (pin "5") (pinfunction "5_5") (pintype "passive"))
      (node (ref "U9") (pin "5") (pinfunction "RXD_5") (pintype "passive"))
    )
    (net (code "39") (name "RCB_GPS1_TP1") (class "Default")
      (node (ref "J6") (pin "6") (pinfunction "6_6") (pintype "passive"))
      (node (ref "U9") (pin "6") (pinfunction "TP1_6") (pintype "passive"))
    )
    (net (code "40") (name "RCB_GPS1_TP2") (class "Default")
      (node (ref "J6") (pin "7") (pinfunction "7_7") (pintype "passive"))
      (node (ref "U9") (pin "7") (pinfunction "TP2_7") (pintype "passive"))
    )
    (net (code "41") (name "RCB_GPS1_TX") (class "Default")
      (node (ref "J6") (pin "3") (pinfunction "3_3") (pintype "passive"))
      (node (ref "U9") (pin "3") (pinfunction "TXD_3") (pintype "passive"))
    )
    (net (code "42") (name "RCB_GPS2_PIN11") (class "Default")
      (node (ref "J13") (pin "11") (pinfunction "11_11") (pintype "passive"))
    )
    (net (code "43") (name "RCB_GPS2_PIN12") (class "Default")
      (node (ref "J13") (pin "12") (pinfunction "12_12") (pintype "passive"))
    )
    (net (code "44") (name "RCB_GPS2_RX") (class "Default")
      (node (ref "J13") (pin "5") (pinfunction "5_5") (pintype "passive"))
      (node (ref "U15") (pin "5") (pinfunction "RXD_5") (pintype "passive"))
    )
    (net (code "45") (name "RCB_GPS2_TP1") (class "Default")
      (node (ref "J13") (pin "6") (pinfunction "6_6") (pintype "passive"))
      (node (ref "U15") (pin "6") (pinfunction "TP1_6") (pintype "passive"))
    )
    (net (code "46") (name "RCB_GPS2_TP2") (class "Default")
      (node (ref "J13") (pin "7") (pinfunction "7_7") (pintype "passive"))
      (node (ref "U15") (pin "7") (pinfunction "TP2_7") (pintype "passive"))
    )
    (net (code "47") (name "RCB_GPS2_TX") (class "Default")
      (node (ref "J13") (pin "3") (pinfunction "3_3") (pintype "passive"))
      (node (ref "U15") (pin "3") (pinfunction "TXD_3") (pintype "passive"))
    )
    (net (code "48") (name "SCL") (class "Default")
      (node (ref "U7") (pin "1") (pinfunction "SCL_1") (pintype "input"))
    )
    (net (code "49") (name "SDA") (class "Default")
      (node (ref "U7") (pin "3") (pinfunction "SDA_3") (pintype "bidirectional"))
    )
    (net (code "50") (name "SENS1_I2C_SCL") (class "Default")
      (node (ref "U13") (pin "19") (pinfunction "COM1_19") (pintype "bidirectional"))
      (node (ref "U14") (pin "4") (pinfunction "SCK_4") (pintype "input"))
    )
    (net (code "51") (name "SENS1_I2C_SDA") (class "Default")
      (node (ref "U13") (pin "20") (pinfunction "COM0_20") (pintype "bidirectional"))
      (node (ref "U14") (pin "3") (pinfunction "SDI_3") (pintype "bidirectional"))
    )
    (net (code "52") (name "unconnected-(U13-NC-Pad1)") (class "Default")
      (node (ref "U13") (pin "1") (pinfunction "NC_1") (pintype "passive"))
    )
    (net (code "53") (name "unconnected-(U13-NC-Pad12)") (class "Default")
      (node (ref "U13") (pin "12") (pinfunction "NC_12") (pintype "passive"))
    )
    (net (code "54") (name "unconnected-(U13-NC-Pad13)") (class "Default")
      (node (ref "U13") (pin "13") (pinfunction "NC_13") (pintype "passive"))
    )
    (net (code "55") (name "unconnected-(U13-NC-Pad15)") (class "Default")
      (node (ref "U13") (pin "15") (pinfunction "NC_15") (pintype "passive"))
    )
    (net (code "56") (name "unconnected-(U13-NC-Pad16)") (class "Default")
      (node (ref "U13") (pin "16") (pinfunction "NC_16") (pintype "passive"))
    )
    (net (code "57") (name "unconnected-(U13-NC-Pad21)") (class "Default")
      (node (ref "U13") (pin "21") (pinfunction "NC_21") (pintype "passive"))
    )
    (net (code "58") (name "unconnected-(U13-NC-Pad22)") (class "Default")
      (node (ref "U13") (pin "22") (pinfunction "NC_22") (pintype "passive"))
    )
    (net (code "59") (name "unconnected-(U13-NC-Pad23)") (class "Default")
      (node (ref "U13") (pin "23") (pinfunction "NC_23") (pintype "passive"))
    )
    (net (code "60") (name "unconnected-(U13-NC-Pad24)") (class "Default")
      (node (ref "U13") (pin "24") (pinfunction "NC_24") (pintype "passive"))
    )
    (net (code "61") (name "unconnected-(U25-NC-Pad5)") (class "Default")
      (node (ref "U25") (pin "5") (pinfunction "NC_5") (pintype "passive"))
    )
  )
)
